# sonar-breakout-thin.net
KiCad netlist of a schematic drawn in EAGLE
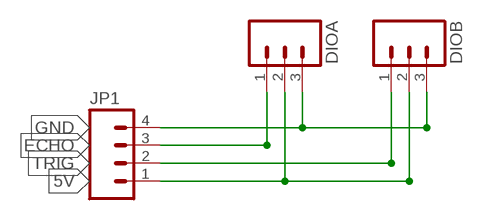
[diagram p0: schematic, sheet 1]

(export (version "E")
  (design (tool "Eeschema 10.0.6"))
  (components
    (comp (ref "DIOA")
      (value "M03LOCK")
      (footprint "eagle-import:1X03_LOCK")
      (libsource (lib "eagle-import") (part "M03LOCK"))
    )
    (comp (ref "DIOB")
      (value "M03LOCK")
      (footprint "eagle-import:1X03_LOCK")
      (libsource (lib "eagle-import") (part "M03LOCK"))
    )
    (comp (ref "JP1")
      (value "M04LOCK")
      (footprint "eagle-import:1X04_LOCK")
      (libsource (lib "eagle-import") (part "M04LOCK"))
    )
  )
  (nets
    (net (code "1") (name "5V") (class "Default")
      (node (ref "DIOA") (pin "2") (pinfunction "2_2") (pintype "passive"))
      (node (ref "DIOB") (pin "2") (pinfunction "2_2") (pintype "passive"))
      (node (ref "JP1") (pin "1") (pinfunction "1_1") (pintype "passive"))
    )
    (net (code "2") (name "ECHO") (class "Default")
      (node (ref "DIOA") (pin "1") (pinfunction "1_1") (pintype "passive"))
      (node (ref "JP1") (pin "3") (pinfunction "3_3") (pintype "passive"))
    )
    (net (code "3") (name "GND") (class "Default")
      (node (ref "DIOA") (pin "3") (pinfunction "3_3") (pintype "passive"))
      (node (ref "DIOB") (pin "3") (pinfunction "3_3") (pintype "passive"))
      (node (ref "JP1") (pin "4") (pinfunction "4_4") (pintype "passive"))
    )
    (net (code "4") (name "TRIG") (class "Default")
      (node (ref "DIOB") (pin "1") (pinfunction "1_1") (pintype "passive"))
      (node (ref "JP1") (pin "2") (pinfunction "2_2") (pintype "passive"))
    )
  )
)
